# yaokong.net
KiCad netlist of a schematic drawn in Altium Designer
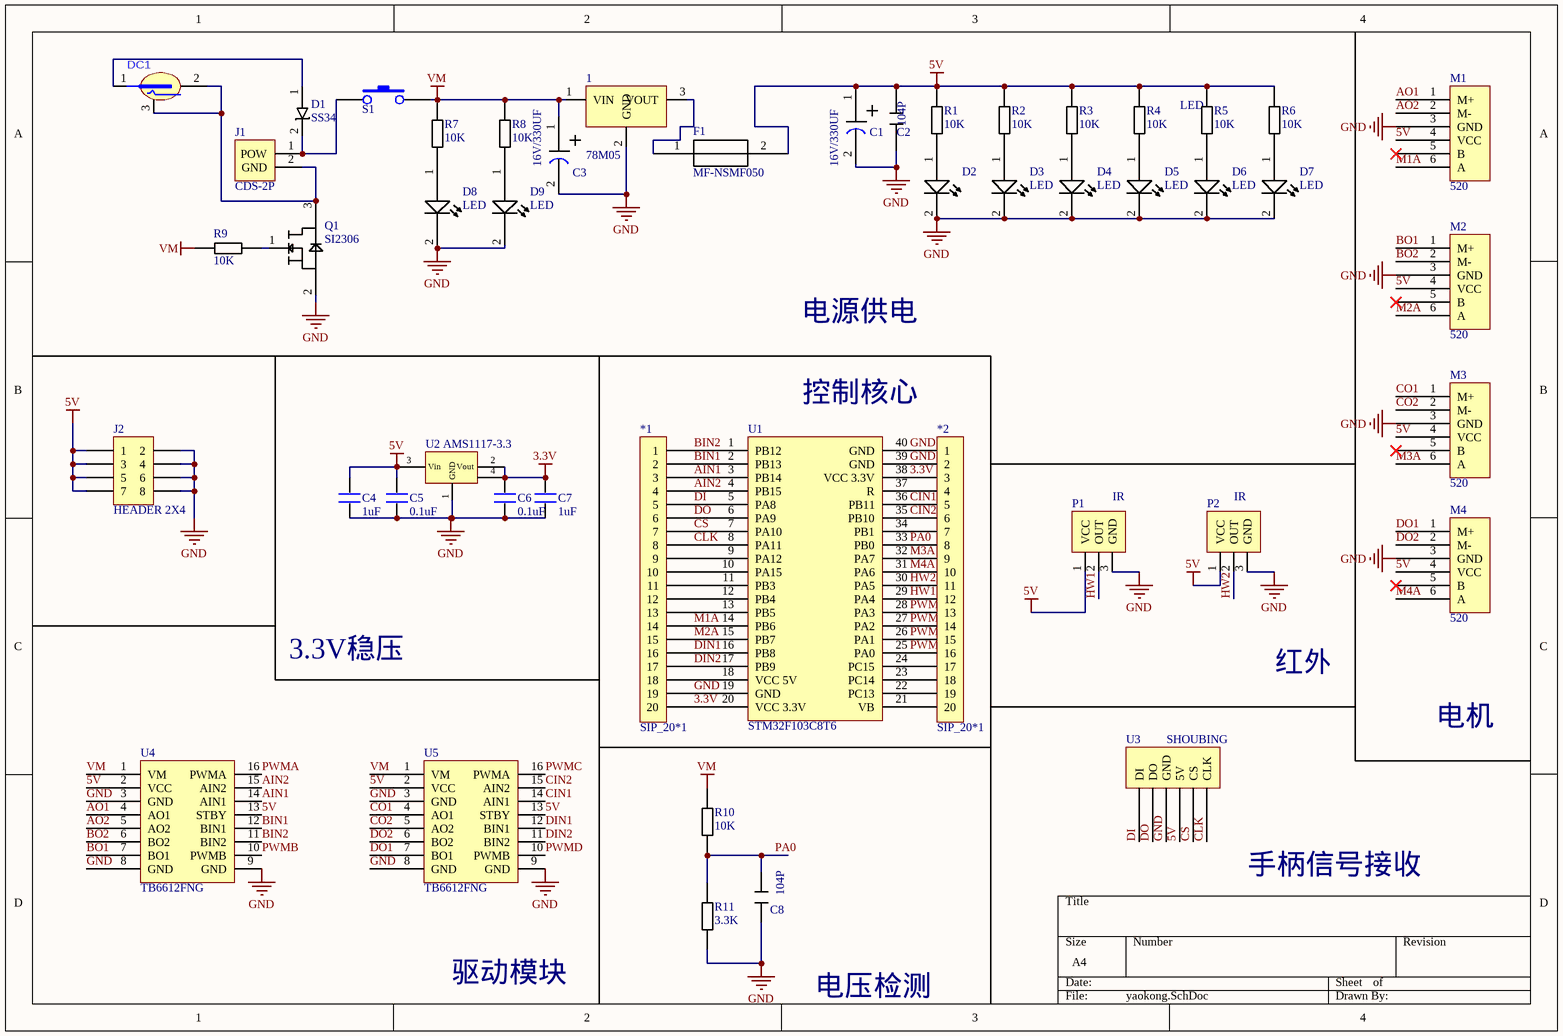
[diagram p0: yaokong.SchDoc]

(export (version "E")
  (design (tool "Eeschema 10.0.6"))
  (components
    (comp (ref "*1")
      (value "SIP_20*1")
      (footprint "HEADER_20")
      (libsource (lib "Connector") (part "SIP_20*1"))
    )
    (comp (ref "*2") (value "SIP_20*1") (footprint "HEADER_20") (libsource (lib "") (part "SIP_20*1_1")))
    (comp (ref "1") (value "78M05") (footprint "78M05") (libsource (lib "yaokong") (part "78M05")))
    (comp (ref "C1") (value "16V/330UF") (footprint "ECAP") (libsource (lib "yaokong") (part "ECAP")))
    (comp (ref "C2") (value "104P") (footprint "CAP") (libsource (lib "") (part "CAP_1")))
    (comp (ref "C3") (value "16V/330UF") (footprint "ECAP") (libsource (lib "yaokong") (part "ECAP")))
    (comp (ref "C4")
      (value "1uF")
      (footprint "0603_棱丝印_2")
      (description "无极性电容")
      (libsource (lib "2019.1.24") (part "CAP"))
    )
    (comp (ref "C5")
      (value "0.1uF")
      (footprint "0603_棱丝印_2")
      (description "无极性电容")
      (libsource (lib "2019.1.24") (part "CAP"))
    )
    (comp (ref "C6")
      (value "0.1uF")
      (footprint "0603_棱丝印_2")
      (description "无极性电容")
      (libsource (lib "2019.1.24") (part "CAP"))
    )
    (comp (ref "C7")
      (value "1uF")
      (footprint "0603_棱丝印_2")
      (description "无极性电容")
      (libsource (lib "2019.1.24") (part "CAP"))
    )
    (comp (ref "C8") (value "104P") (footprint "CAP") (libsource (lib "yaokong") (part "CAP")))
    (comp (ref "D1") (value "SS34") (footprint "SS34") (libsource (lib "yaokong") (part "SS34")))
    (comp (ref "D2") (value "LED") (footprint "0603_棱丝印_2") (libsource (lib "yaokong") (part "LED")))
    (comp (ref "D3") (value "LED") (footprint "0603_棱丝印_2") (libsource (lib "yaokong") (part "LED")))
    (comp (ref "D4") (value "LED") (footprint "0603_棱丝印_2") (libsource (lib "yaokong") (part "LED")))
    (comp (ref "D5") (value "LED") (footprint "0603_棱丝印_2") (libsource (lib "yaokong") (part "LED")))
    (comp (ref "D6") (value "LED") (footprint "0603_棱丝印_2") (libsource (lib "yaokong") (part "LED")))
    (comp (ref "D7") (value "LED") (footprint "0603_棱丝印_2") (libsource (lib "yaokong") (part "LED")))
    (comp (ref "D8") (value "LED") (footprint "0603_棱丝印_2") (libsource (lib "") (part "LED_1")))
    (comp (ref "D9") (value "LED") (footprint "0603_棱丝印_2") (libsource (lib "") (part "LED_1")))
    (comp (ref "DC1")
      (value "DC005")
      (footprint "DC-IN_3P-DC-005-5A-3.0")
      (description "DC005电源接口")
      (libsource (lib "Connector") (part "DC005"))
    )
    (comp (ref "F1") (value "MF-NSMF050") (footprint "MF") (libsource (lib "yaokong") (part "MF-NSMF050")))
    (comp (ref "J1") (value "CDS-2P") (footprint "CDS-2P") (libsource (lib "yaokong") (part "CDS-2P")))
    (comp (ref "J2")
      (value "HEADER 2X4")
      (footprint "HEADER2*4")
      (libsource (lib "yaokong") (part "HEADER 2X4"))
    )
    (comp (ref "M1") (value "520") (footprint "PH2.0-6P") (libsource (lib "yaokong") (part "dianji")))
    (comp (ref "M2") (value "520") (footprint "PH2.0-6P") (libsource (lib "yaokong") (part "dianji")))
    (comp (ref "M3") (value "520") (footprint "PH2.0-6P") (libsource (lib "yaokong") (part "dianji")))
    (comp (ref "M4") (value "520") (footprint "PH2.0-6P") (libsource (lib "yaokong") (part "dianji")))
    (comp (ref "P1") (value "IR") (footprint "HEADER3") (libsource (lib "yaokong") (part "IR")))
    (comp (ref "P2") (value "IR") (footprint "HEADER3") (libsource (lib "yaokong") (part "IR")))
    (comp (ref "Q1") (value "SI2306") (footprint "SI2306") (libsource (lib "yaokong") (part "SI2306")))
    (comp (ref "R1") (value "10K") (footprint "0603_棱丝印_2") (libsource (lib "yaokong") (part "RES")))
    (comp (ref "R2") (value "10K") (footprint "0603_棱丝印_2") (libsource (lib "yaokong") (part "RES")))
    (comp (ref "R3") (value "10K") (footprint "0603_棱丝印_2") (libsource (lib "yaokong") (part "RES")))
    (comp (ref "R4") (value "10K") (footprint "0603_棱丝印_2") (libsource (lib "yaokong") (part "RES")))
    (comp (ref "R5") (value "10K") (footprint "0603_棱丝印_2") (libsource (lib "yaokong") (part "RES")))
    (comp (ref "R6") (value "10K") (footprint "0603_棱丝印_2") (libsource (lib "yaokong") (part "RES")))
    (comp (ref "R7") (value "10K") (footprint "0603_棱丝印_2") (libsource (lib "yaokong") (part "RES")))
    (comp (ref "R8") (value "10K") (footprint "0603_棱丝印_2") (libsource (lib "yaokong") (part "RES")))
    (comp (ref "R9") (value "10K") (footprint "0603_棱丝印_2") (libsource (lib "yaokong") (part "RES")))
    (comp (ref "R10") (value "10K") (footprint "0603_棱丝印_2") (libsource (lib "yaokong") (part "RES")))
    (comp (ref "R11") (value "3.3K") (footprint "0603_棱丝印_2") (libsource (lib "yaokong") (part "RES")))
    (comp (ref "S1") (value "KEY") (footprint "KCD-11 2P") (libsource (lib "2019.1.24") (part "KEY")))
    (comp (ref "U1")
      (value "STM32F103C8T6")
      (footprint "STM32F103C8T6")
      (libsource (lib "yaokong") (part "STM32F103C8T6"))
    )
    (comp (ref "U2")
      (value "AMS1117-3.3")
      (footprint "AMS1117-3.3")
      (description "3.3V稳压")
      (libsource (lib "2019.1.24") (part "AMS1117-3.3"))
    )
    (comp (ref "U3") (value "SHOUBING") (footprint "SHOUBING") (libsource (lib "yaokong") (part "SHOUBING")))
    (comp (ref "U4")
      (value "TB6612FNG")
      (footprint "TB6612FNG")
      (libsource (lib "yaokong") (part "TB6612FNG"))
    )
    (comp (ref "U5")
      (value "TB6612FNG")
      (footprint "TB6612FNG")
      (libsource (lib "yaokong") (part "TB6612FNG"))
    )
  )
  (nets
    (net (code "1") (name "/AIN1") (class "Default")
      (node (ref "*1") (pin "3") (pinfunction "3_3") (pintype "passive"))
      (node (ref "U1") (pin "3") (pinfunction "PB14_3") (pintype "passive"))
      (node (ref "U4") (pin "14") (pinfunction "AIN1_14") (pintype "passive"))
    )
    (net (code "2") (name "/AIN2") (class "Default")
      (node (ref "*1") (pin "4") (pinfunction "4_4") (pintype "passive"))
      (node (ref "U1") (pin "4") (pinfunction "PB15_4") (pintype "passive"))
      (node (ref "U4") (pin "15") (pinfunction "AIN2_15") (pintype "passive"))
    )
    (net (code "3") (name "/AO1") (class "Default")
      (node (ref "M1") (pin "1") (pinfunction "M+_1") (pintype "passive"))
      (node (ref "U4") (pin "4") (pinfunction "AO1_4") (pintype "passive"))
    )
    (net (code "4") (name "/AO2") (class "Default")
      (node (ref "M1") (pin "2") (pinfunction "M-_2") (pintype "passive"))
      (node (ref "U4") (pin "5") (pinfunction "AO2_5") (pintype "passive"))
    )
    (net (code "5") (name "/BIN1") (class "Default")
      (node (ref "*1") (pin "2") (pinfunction "2_2") (pintype "passive"))
      (node (ref "U1") (pin "2") (pinfunction "PB13_2") (pintype "passive"))
      (node (ref "U4") (pin "12") (pinfunction "BIN1_12") (pintype "passive"))
    )
    (net (code "6") (name "/BIN2") (class "Default")
      (node (ref "*1") (pin "1") (pinfunction "1_1") (pintype "passive"))
      (node (ref "U1") (pin "1") (pinfunction "PB12_1") (pintype "passive"))
      (node (ref "U4") (pin "11") (pinfunction "BIN2_11") (pintype "passive"))
    )
    (net (code "7") (name "/BO1") (class "Default")
      (node (ref "M2") (pin "1") (pinfunction "M+_1") (pintype "passive"))
      (node (ref "U4") (pin "7") (pinfunction "BO1_7") (pintype "passive"))
    )
    (net (code "8") (name "/BO2") (class "Default")
      (node (ref "M2") (pin "2") (pinfunction "M-_2") (pintype "passive"))
      (node (ref "U4") (pin "6") (pinfunction "BO2_6") (pintype "passive"))
    )
    (net (code "9") (name "/CIN1") (class "Default")
      (node (ref "*2") (pin "5") (pinfunction "5_5") (pintype "passive"))
      (node (ref "U1") (pin "36") (pinfunction "PB11_36") (pintype "passive"))
      (node (ref "U5") (pin "14") (pinfunction "AIN1_14") (pintype "passive"))
    )
    (net (code "10") (name "/CIN2") (class "Default")
      (node (ref "*2") (pin "6") (pinfunction "6_6") (pintype "passive"))
      (node (ref "U1") (pin "35") (pinfunction "PB10_35") (pintype "passive"))
      (node (ref "U5") (pin "15") (pinfunction "AIN2_15") (pintype "passive"))
    )
    (net (code "11") (name "/CLK") (class "Default")
      (node (ref "*1") (pin "8") (pinfunction "8_8") (pintype "passive"))
      (node (ref "U1") (pin "8") (pinfunction "PA11_8") (pintype "passive"))
      (node (ref "U3") (pin "6") (pinfunction "CLK_6") (pintype "passive"))
    )
    (net (code "12") (name "/CO1") (class "Default")
      (node (ref "M3") (pin "1") (pinfunction "M+_1") (pintype "passive"))
      (node (ref "U5") (pin "4") (pinfunction "AO1_4") (pintype "passive"))
    )
    (net (code "13") (name "/CO2") (class "Default")
      (node (ref "M3") (pin "2") (pinfunction "M-_2") (pintype "passive"))
      (node (ref "U5") (pin "5") (pinfunction "AO2_5") (pintype "passive"))
    )
    (net (code "14") (name "/CS") (class "Default")
      (node (ref "*1") (pin "7") (pinfunction "7_7") (pintype "passive"))
      (node (ref "U1") (pin "7") (pinfunction "PA10_7") (pintype "passive"))
      (node (ref "U3") (pin "5") (pinfunction "CS_5") (pintype "passive"))
    )
    (net (code "15") (name "/DI") (class "Default")
      (node (ref "*1") (pin "5") (pinfunction "5_5") (pintype "passive"))
      (node (ref "U1") (pin "5") (pinfunction "PA8_5") (pintype "passive"))
      (node (ref "U3") (pin "1") (pinfunction "DI_1") (pintype "passive"))
    )
    (net (code "16") (name "/DIN1") (class "Default")
      (node (ref "*1") (pin "16") (pinfunction "16_16") (pintype "passive"))
      (node (ref "U1") (pin "16") (pinfunction "PB8_16") (pintype "passive"))
      (node (ref "U5") (pin "12") (pinfunction "BIN1_12") (pintype "passive"))
    )
    (net (code "17") (name "/DIN2") (class "Default")
      (node (ref "*1") (pin "17") (pinfunction "17_17") (pintype "passive"))
      (node (ref "U1") (pin "17") (pinfunction "PB9_17") (pintype "passive"))
      (node (ref "U5") (pin "11") (pinfunction "BIN2_11") (pintype "passive"))
    )
    (net (code "18") (name "/DO") (class "Default")
      (node (ref "*1") (pin "6") (pinfunction "6_6") (pintype "passive"))
      (node (ref "U1") (pin "6") (pinfunction "PA9_6") (pintype "passive"))
      (node (ref "U3") (pin "2") (pinfunction "DO_2") (pintype "passive"))
    )
    (net (code "19") (name "/DO1") (class "Default")
      (node (ref "M4") (pin "1") (pinfunction "M+_1") (pintype "passive"))
      (node (ref "U5") (pin "7") (pinfunction "BO1_7") (pintype "passive"))
    )
    (net (code "20") (name "/DO2") (class "Default")
      (node (ref "M4") (pin "2") (pinfunction "M-_2") (pintype "passive"))
      (node (ref "U5") (pin "6") (pinfunction "BO2_6") (pintype "passive"))
    )
    (net (code "21") (name "/HW1") (class "Default")
      (node (ref "*2") (pin "12") (pinfunction "12_12") (pintype "passive"))
      (node (ref "P1") (pin "2") (pinfunction "OUT_2") (pintype "passive"))
      (node (ref "U1") (pin "29") (pinfunction "PA4_29") (pintype "passive"))
    )
    (net (code "22") (name "/HW2") (class "Default")
      (node (ref "*2") (pin "11") (pinfunction "11_11") (pintype "passive"))
      (node (ref "P2") (pin "2") (pinfunction "OUT_2") (pintype "passive"))
      (node (ref "U1") (pin "30") (pinfunction "PA5_30") (pintype "passive"))
    )
    (net (code "23") (name "/M1A") (class "Default")
      (node (ref "*1") (pin "14") (pinfunction "14_14") (pintype "passive"))
      (node (ref "M1") (pin "6") (pinfunction "A_6") (pintype "passive"))
      (node (ref "U1") (pin "14") (pinfunction "PB6_14") (pintype "passive"))
    )
    (net (code "24") (name "/M2A") (class "Default")
      (node (ref "*1") (pin "15") (pinfunction "15_15") (pintype "passive"))
      (node (ref "M2") (pin "6") (pinfunction "A_6") (pintype "passive"))
      (node (ref "U1") (pin "15") (pinfunction "PB7_15") (pintype "passive"))
    )
    (net (code "25") (name "/M3A") (class "Default")
      (node (ref "*2") (pin "9") (pinfunction "9_9") (pintype "passive"))
      (node (ref "M3") (pin "6") (pinfunction "A_6") (pintype "passive"))
      (node (ref "U1") (pin "32") (pinfunction "PA7_32") (pintype "passive"))
    )
    (net (code "26") (name "/M4A") (class "Default")
      (node (ref "*2") (pin "10") (pinfunction "10_10") (pintype "passive"))
      (node (ref "M4") (pin "6") (pinfunction "A_6") (pintype "passive"))
      (node (ref "U1") (pin "31") (pinfunction "PA6_31") (pintype "passive"))
    )
    (net (code "27") (name "/PA0") (class "Default")
      (node (ref "*2") (pin "8") (pinfunction "8_8") (pintype "passive"))
      (node (ref "C8") (pin "2") (pintype "passive"))
      (node (ref "R10") (pin "1") (pintype "passive"))
      (node (ref "R11") (pin "2") (pintype "passive"))
      (node (ref "U1") (pin "33") (pinfunction "PB0_33") (pintype "passive"))
    )
    (net (code "28") (name "/PWMA") (class "Default")
      (node (ref "*2") (pin "14") (pinfunction "14_14") (pintype "passive"))
      (node (ref "U1") (pin "27") (pinfunction "PA2_27") (pintype "passive"))
      (node (ref "U4") (pin "16") (pinfunction "PWMA_16") (pintype "passive"))
    )
    (net (code "29") (name "/PWMB") (class "Default")
      (node (ref "*2") (pin "13") (pinfunction "13_13") (pintype "passive"))
      (node (ref "U1") (pin "28") (pinfunction "PA3_28") (pintype "passive"))
      (node (ref "U4") (pin "10") (pinfunction "PWMB_10") (pintype "passive"))
    )
    (net (code "30") (name "/PWMC") (class "Default")
      (node (ref "*2") (pin "15") (pinfunction "15_15") (pintype "passive"))
      (node (ref "U1") (pin "26") (pinfunction "PA1_26") (pintype "passive"))
      (node (ref "U5") (pin "16") (pinfunction "PWMA_16") (pintype "passive"))
    )
    (net (code "31") (name "/PWMD") (class "Default")
      (node (ref "*2") (pin "16") (pinfunction "16_16") (pintype "passive"))
      (node (ref "U1") (pin "25") (pinfunction "PA0_25") (pintype "passive"))
      (node (ref "U5") (pin "10") (pinfunction "PWMB_10") (pintype "passive"))
    )
    (net (code "32") (name "3.3V") (class "Default")
      (node (ref "*1") (pin "20") (pinfunction "20_20") (pintype "passive"))
      (node (ref "*2") (pin "3") (pinfunction "3_3") (pintype "passive"))
      (node (ref "C6") (pin "2") (pintype "passive"))
      (node (ref "C7") (pin "2") (pintype "passive"))
      (node (ref "U1") (pin "20") (pinfunction "VCC_3.3V_20") (pintype "passive"))
      (node (ref "U1") (pin "38") (pinfunction "VCC_3.3V_38") (pintype "passive"))
      (node (ref "U2") (pin "2") (pinfunction "Vout_2") (pintype "passive"))
      (node (ref "U2") (pin "4") (pinfunction "Vout_4") (pintype "passive"))
    )
    (net (code "33") (name "5V") (class "Default")
      (node (ref "C1") (pin "1") (pintype "passive"))
      (node (ref "C2") (pin "2") (pintype "passive"))
      (node (ref "C4") (pin "2") (pintype "passive"))
      (node (ref "C5") (pin "2") (pintype "passive"))
      (node (ref "F1") (pin "2") (pintype "passive"))
      (node (ref "J2") (pin "1") (pinfunction "1_1") (pintype "passive"))
      (node (ref "J2") (pin "3") (pinfunction "3_3") (pintype "passive"))
      (node (ref "J2") (pin "5") (pinfunction "5_5") (pintype "passive"))
      (node (ref "J2") (pin "7") (pinfunction "7_7") (pintype "passive"))
      (node (ref "M1") (pin "4") (pinfunction "VCC_4") (pintype "passive"))
      (node (ref "M2") (pin "4") (pinfunction "VCC_4") (pintype "passive"))
      (node (ref "M3") (pin "4") (pinfunction "VCC_4") (pintype "passive"))
      (node (ref "M4") (pin "4") (pinfunction "VCC_4") (pintype "passive"))
      (node (ref "P1") (pin "1") (pinfunction "VCC_1") (pintype "passive"))
      (node (ref "P2") (pin "1") (pinfunction "VCC_1") (pintype "passive"))
      (node (ref "R1") (pin "2") (pintype "passive"))
      (node (ref "R2") (pin "2") (pintype "passive"))
      (node (ref "R3") (pin "2") (pintype "passive"))
      (node (ref "R4") (pin "2") (pintype "passive"))
      (node (ref "R5") (pin "2") (pintype "passive"))
      (node (ref "R6") (pin "2") (pintype "passive"))
      (node (ref "U2") (pin "3") (pinfunction "Vin_3") (pintype "passive"))
      (node (ref "U3") (pin "4") (pinfunction "5V_4") (pintype "passive"))
      (node (ref "U4") (pin "13") (pinfunction "STBY_13") (pintype "passive"))
      (node (ref "U4") (pin "2") (pinfunction "VCC_2") (pintype "passive"))
      (node (ref "U5") (pin "13") (pinfunction "STBY_13") (pintype "passive"))
      (node (ref "U5") (pin "2") (pinfunction "VCC_2") (pintype "passive"))
    )
    (net (code "34") (name "GND") (class "Default")
      (node (ref "*1") (pin "19") (pinfunction "19_19") (pintype "passive"))
      (node (ref "*2") (pin "1") (pinfunction "1_1") (pintype "passive"))
      (node (ref "*2") (pin "2") (pinfunction "2_2") (pintype "passive"))
      (node (ref "1") (pin "2") (pinfunction "GND_2") (pintype "passive"))
      (node (ref "C1") (pin "2") (pintype "passive"))
      (node (ref "C2") (pin "1") (pintype "passive"))
      (node (ref "C3") (pin "2") (pintype "passive"))
      (node (ref "C4") (pin "1") (pintype "passive"))
      (node (ref "C5") (pin "1") (pintype "passive"))
      (node (ref "C6") (pin "1") (pintype "passive"))
      (node (ref "C7") (pin "1") (pintype "passive"))
      (node (ref "C8") (pin "1") (pintype "passive"))
      (node (ref "D2") (pin "2") (pintype "passive"))
      (node (ref "D3") (pin "2") (pintype "passive"))
      (node (ref "D4") (pin "2") (pintype "passive"))
      (node (ref "D5") (pin "2") (pintype "passive"))
      (node (ref "D6") (pin "2") (pintype "passive"))
      (node (ref "D7") (pin "2") (pintype "passive"))
      (node (ref "D8") (pin "2") (pintype "passive"))
      (node (ref "D9") (pin "2") (pintype "passive"))
      (node (ref "J2") (pin "2") (pinfunction "2_2") (pintype "passive"))
      (node (ref "J2") (pin "4") (pinfunction "4_4") (pintype "passive"))
      (node (ref "J2") (pin "6") (pinfunction "6_6") (pintype "passive"))
      (node (ref "J2") (pin "8") (pinfunction "8_8") (pintype "passive"))
      (node (ref "M1") (pin "3") (pinfunction "GND_3") (pintype "passive"))
      (node (ref "M2") (pin "3") (pinfunction "GND_3") (pintype "passive"))
      (node (ref "M3") (pin "3") (pinfunction "GND_3") (pintype "passive"))
      (node (ref "M4") (pin "3") (pinfunction "GND_3") (pintype "passive"))
      (node (ref "P1") (pin "3") (pinfunction "GND_3") (pintype "passive"))
      (node (ref "P2") (pin "3") (pinfunction "GND_3") (pintype "passive"))
      (node (ref "Q1") (pin "2") (pintype "passive"))
      (node (ref "R11") (pin "1") (pintype "passive"))
      (node (ref "U1") (pin "19") (pinfunction "GND_19") (pintype "passive"))
      (node (ref "U1") (pin "39") (pinfunction "GND_39") (pintype "passive"))
      (node (ref "U1") (pin "40") (pinfunction "GND_40") (pintype "passive"))
      (node (ref "U2") (pin "1") (pinfunction "GND_1") (pintype "passive"))
      (node (ref "U3") (pin "3") (pinfunction "GND_3") (pintype "passive"))
      (node (ref "U4") (pin "3") (pinfunction "GND_3") (pintype "passive"))
      (node (ref "U4") (pin "8") (pinfunction "GND_8") (pintype "passive"))
      (node (ref "U4") (pin "9") (pinfunction "GND_9") (pintype "passive"))
      (node (ref "U5") (pin "3") (pinfunction "GND_3") (pintype "passive"))
      (node (ref "U5") (pin "8") (pinfunction "GND_8") (pintype "passive"))
      (node (ref "U5") (pin "9") (pinfunction "GND_9") (pintype "passive"))
    )
    (net (code "35") (name "Net-(1-VOUT)") (class "Default")
      (node (ref "1") (pin "3") (pinfunction "VOUT_3") (pintype "passive"))
      (node (ref "F1") (pin "1") (pintype "passive"))
    )
    (net (code "36") (name "Net-(D1-Pad1)") (class "Default")
      (node (ref "D1") (pin "1") (pintype "passive"))
      (node (ref "DC1") (pin "1") (pintype "passive"))
    )
    (net (code "37") (name "Net-(D2-Pad1)") (class "Default")
      (node (ref "D2") (pin "1") (pintype "passive"))
      (node (ref "R1") (pin "1") (pintype "passive"))
    )
    (net (code "38") (name "Net-(D3-Pad1)") (class "Default")
      (node (ref "D3") (pin "1") (pintype "passive"))
      (node (ref "R2") (pin "1") (pintype "passive"))
    )
    (net (code "39") (name "Net-(D4-Pad1)") (class "Default")
      (node (ref "D4") (pin "1") (pintype "passive"))
      (node (ref "R3") (pin "1") (pintype "passive"))
    )
    (net (code "40") (name "Net-(D5-Pad1)") (class "Default")
      (node (ref "D5") (pin "1") (pintype "passive"))
      (node (ref "R4") (pin "1") (pintype "passive"))
    )
    (net (code "41") (name "Net-(D6-Pad1)") (class "Default")
      (node (ref "D6") (pin "1") (pintype "passive"))
      (node (ref "R5") (pin "1") (pintype "passive"))
    )
    (net (code "42") (name "Net-(D7-Pad1)") (class "Default")
      (node (ref "D7") (pin "1") (pintype "passive"))
      (node (ref "R6") (pin "1") (pintype "passive"))
    )
    (net (code "43") (name "Net-(D8-Pad1)") (class "Default")
      (node (ref "D8") (pin "1") (pintype "passive"))
      (node (ref "R7") (pin "1") (pintype "passive"))
    )
    (net (code "44") (name "Net-(D9-Pad1)") (class "Default")
      (node (ref "D9") (pin "1") (pintype "passive"))
      (node (ref "R8") (pin "1") (pintype "passive"))
    )
    (net (code "45") (name "Net-(J1-GND)") (class "Default")
      (node (ref "DC1") (pin "2") (pintype "passive"))
      (node (ref "DC1") (pin "3") (pintype "passive"))
      (node (ref "J1") (pin "2") (pinfunction "GND_2") (pintype "passive"))
      (node (ref "Q1") (pin "3") (pintype "passive"))
    )
    (net (code "46") (name "Net-(J1-POW)") (class "Default")
      (node (ref "D1") (pin "2") (pintype "passive"))
      (node (ref "J1") (pin "1") (pinfunction "POW_1") (pintype "passive"))
      (node (ref "S1") (pin "1") (pinfunction "1_1") (pintype "passive"))
    )
    (net (code "47") (name "Net-(Q1-Pad1)") (class "Default")
      (node (ref "Q1") (pin "1") (pintype "passive"))
      (node (ref "R9") (pin "2") (pintype "passive"))
    )
    (net (code "48") (name "Net-(U1-PA12)") (class "Default")
      (node (ref "*1") (pin "9") (pinfunction "9_9") (pintype "passive"))
      (node (ref "U1") (pin "9") (pinfunction "PA12_9") (pintype "passive"))
    )
    (net (code "49") (name "Net-(U1-PA15)") (class "Default")
      (node (ref "*1") (pin "10") (pinfunction "10_10") (pintype "passive"))
      (node (ref "U1") (pin "10") (pinfunction "PA15_10") (pintype "passive"))
    )
    (net (code "50") (name "Net-(U1-PB1)") (class "Default")
      (node (ref "*2") (pin "7") (pinfunction "7_7") (pintype "passive"))
      (node (ref "U1") (pin "34") (pinfunction "PB1_34") (pintype "passive"))
    )
    (net (code "51") (name "Net-(U1-PB3)") (class "Default")
      (node (ref "*1") (pin "11") (pinfunction "11_11") (pintype "passive"))
      (node (ref "U1") (pin "11") (pinfunction "PB3_11") (pintype "passive"))
    )
    (net (code "52") (name "Net-(U1-PB4)") (class "Default")
      (node (ref "*1") (pin "12") (pinfunction "12_12") (pintype "passive"))
      (node (ref "U1") (pin "12") (pinfunction "PB4_12") (pintype "passive"))
    )
    (net (code "53") (name "Net-(U1-PB5)") (class "Default")
      (node (ref "*1") (pin "13") (pinfunction "13_13") (pintype "passive"))
      (node (ref "U1") (pin "13") (pinfunction "PB5_13") (pintype "passive"))
    )
    (net (code "54") (name "Net-(U1-PC13)") (class "Default")
      (node (ref "*2") (pin "19") (pinfunction "19_19") (pintype "passive"))
      (node (ref "U1") (pin "22") (pinfunction "PC13_22") (pintype "passive"))
    )
    (net (code "55") (name "Net-(U1-PC14)") (class "Default")
      (node (ref "*2") (pin "18") (pinfunction "18_18") (pintype "passive"))
      (node (ref "U1") (pin "23") (pinfunction "PC14_23") (pintype "passive"))
    )
    (net (code "56") (name "Net-(U1-PC15)") (class "Default")
      (node (ref "*2") (pin "17") (pinfunction "17_17") (pintype "passive"))
      (node (ref "U1") (pin "24") (pinfunction "PC15_24") (pintype "passive"))
    )
    (net (code "57") (name "Net-(U1-R)") (class "Default")
      (node (ref "*2") (pin "4") (pinfunction "4_4") (pintype "passive"))
      (node (ref "U1") (pin "37") (pinfunction "R_37") (pintype "passive"))
    )
    (net (code "58") (name "Net-(U1-VB)") (class "Default")
      (node (ref "*2") (pin "20") (pinfunction "20_20") (pintype "passive"))
      (node (ref "U1") (pin "21") (pinfunction "VB_21") (pintype "passive"))
    )
    (net (code "59") (name "Net-(U1-VCC_5V)") (class "Default")
      (node (ref "*1") (pin "18") (pinfunction "18_18") (pintype "passive"))
      (node (ref "U1") (pin "18") (pinfunction "VCC_5V_18") (pintype "passive"))
    )
    (net (code "60") (name "VM") (class "Default")
      (node (ref "1") (pin "1") (pinfunction "VIN_1") (pintype "passive"))
      (node (ref "C3") (pin "1") (pintype "passive"))
      (node (ref "R10") (pin "2") (pintype "passive"))
      (node (ref "R7") (pin "2") (pintype "passive"))
      (node (ref "R8") (pin "2") (pintype "passive"))
      (node (ref "R9") (pin "1") (pintype "passive"))
      (node (ref "S1") (pin "2") (pinfunction "2_2") (pintype "passive"))
      (node (ref "U4") (pin "1") (pinfunction "VM_1") (pintype "passive"))
      (node (ref "U5") (pin "1") (pinfunction "VM_1") (pintype "passive"))
    )
    (net (code "61") (name "unconnected-(M1-B-Pad5)") (class "Default")
      (node (ref "M1") (pin "5") (pinfunction "B_5") (pintype "passive+no_connect"))
    )
    (net (code "62") (name "unconnected-(M2-B-Pad5)") (class "Default")
      (node (ref "M2") (pin "5") (pinfunction "B_5") (pintype "passive+no_connect"))
    )
    (net (code "63") (name "unconnected-(M3-B-Pad5)") (class "Default")
      (node (ref "M3") (pin "5") (pinfunction "B_5") (pintype "passive+no_connect"))
    )
    (net (code "64") (name "unconnected-(M4-B-Pad5)") (class "Default")
      (node (ref "M4") (pin "5") (pinfunction "B_5") (pintype "passive+no_connect"))
    )
  )
)
